# nixie_with_colon.net
KiCad netlist of a schematic drawn in EAGLE
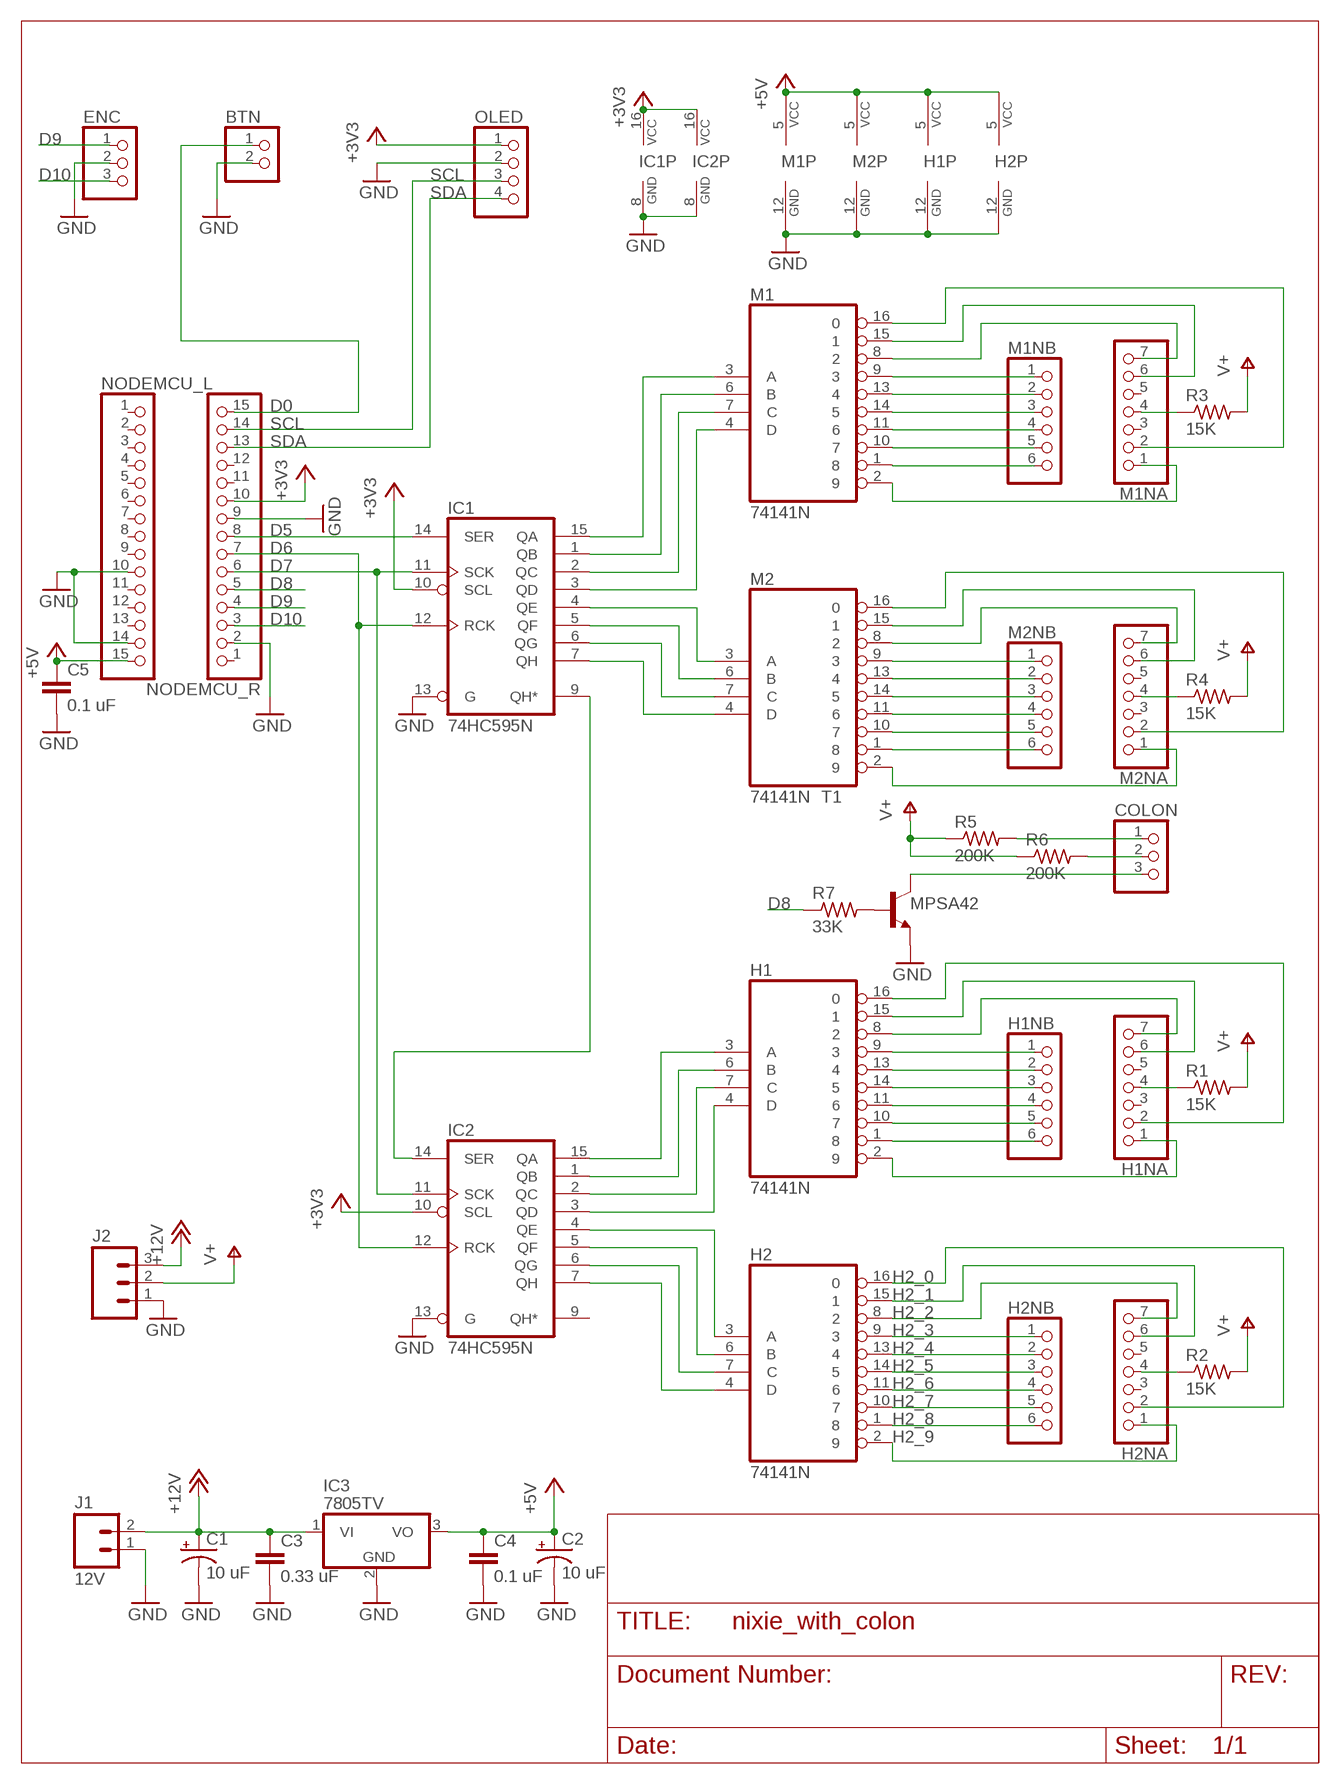
[diagram p0: schematic, sheet 1]

(export (version "E")
  (design (tool "Eeschema 10.0.6"))
  (components
    (comp (ref "BTN")
      (value "PINHD-1X2")
      (footprint "eagle-import:1X02")
      (libsource (lib "eagle-import") (part "PINHD-1X2"))
    )
    (comp (ref "C1")
      (value "10 uF")
      (footprint "eagle-import:E2,5-6")
      (libsource (lib "eagle-import") (part "CPOL-USE2.5-6"))
    )
    (comp (ref "C2")
      (value "10 uF")
      (footprint "eagle-import:E2,5-6")
      (libsource (lib "eagle-import") (part "CPOL-USE2.5-6"))
    )
    (comp (ref "C3")
      (value "0.33 uF")
      (footprint "eagle-import:C050-025X075")
      (libsource (lib "eagle-import") (part "C-EU050-025X075"))
    )
    (comp (ref "C4")
      (value "0.1 uF")
      (footprint "eagle-import:C050-025X075")
      (libsource (lib "eagle-import") (part "C-EU050-025X075"))
    )
    (comp (ref "C5")
      (value "0.1 uF")
      (footprint "eagle-import:C050-025X075")
      (libsource (lib "eagle-import") (part "C-EU050-025X075"))
    )
    (comp (ref "COLON")
      (value "PINHD-1X3")
      (footprint "eagle-import:1X03")
      (libsource (lib "eagle-import") (part "PINHD-1X3"))
    )
    (comp (ref "ENC")
      (value "PINHD-1X3")
      (footprint "eagle-import:1X03")
      (libsource (lib "eagle-import") (part "PINHD-1X3"))
    )
    (comp (ref "H1")
      (value "74141N")
      (footprint "eagle-import:DIL16")
      (libsource (lib "eagle-import") (part "74141N"))
    )
    (comp (ref "H1NA")
      (value "PINHD-1X7")
      (footprint "eagle-import:1X07")
      (libsource (lib "eagle-import") (part "PINHD-1X7"))
    )
    (comp (ref "H1NB")
      (value "PINHD-1X6")
      (footprint "eagle-import:1X06")
      (libsource (lib "eagle-import") (part "PINHD-1X6"))
    )
    (comp (ref "H2")
      (value "74141N")
      (footprint "eagle-import:DIL16")
      (libsource (lib "eagle-import") (part "74141N"))
    )
    (comp (ref "H2NA")
      (value "PINHD-1X7")
      (footprint "eagle-import:1X07")
      (libsource (lib "eagle-import") (part "PINHD-1X7"))
    )
    (comp (ref "H2NB")
      (value "PINHD-1X6")
      (footprint "eagle-import:1X06")
      (libsource (lib "eagle-import") (part "PINHD-1X6"))
    )
    (comp (ref "IC1")
      (value "74HC595N")
      (footprint "eagle-import:DIL16")
      (libsource (lib "eagle-import") (part "74595NHC"))
    )
    (comp (ref "IC2")
      (value "74HC595N")
      (footprint "eagle-import:DIL16")
      (libsource (lib "eagle-import") (part "74595NHC"))
    )
    (comp (ref "IC3")
      (value "7805TV")
      (footprint "eagle-import:TO220V")
      (libsource (lib "eagle-import") (part "78TV05"))
    )
    (comp (ref "J1")
      (value "12V")
      (footprint "eagle-import:SCREWTERMINAL-5MM-2")
      (libsource (lib "eagle-import") (part "M025MM"))
    )
    (comp (ref "J2")
      (value "M03-SCREW-5MM")
      (footprint "eagle-import:SCREWTERMINAL-5MM-3")
      (libsource (lib "eagle-import") (part "M03-SCREW-5MM"))
    )
    (comp (ref "M1")
      (value "74141N")
      (footprint "eagle-import:DIL16")
      (libsource (lib "eagle-import") (part "74141N"))
    )
    (comp (ref "M1NA")
      (value "PINHD-1X7")
      (footprint "eagle-import:1X07")
      (libsource (lib "eagle-import") (part "PINHD-1X7"))
    )
    (comp (ref "M1NB")
      (value "PINHD-1X6")
      (footprint "eagle-import:1X06")
      (libsource (lib "eagle-import") (part "PINHD-1X6"))
    )
    (comp (ref "M2")
      (value "74141N")
      (footprint "eagle-import:DIL16")
      (libsource (lib "eagle-import") (part "74141N"))
    )
    (comp (ref "M2NA")
      (value "PINHD-1X7")
      (footprint "eagle-import:1X07")
      (libsource (lib "eagle-import") (part "PINHD-1X7"))
    )
    (comp (ref "M2NB")
      (value "PINHD-1X6")
      (footprint "eagle-import:1X06")
      (libsource (lib "eagle-import") (part "PINHD-1X6"))
    )
    (comp (ref "NODEMCU_L")
      (value "PINHD-1X15")
      (footprint "eagle-import:1X15")
      (libsource (lib "eagle-import") (part "PINHD-1X15"))
    )
    (comp (ref "NODEMCU_R")
      (value "PINHD-1X15")
      (footprint "eagle-import:1X15")
      (libsource (lib "eagle-import") (part "PINHD-1X15"))
    )
    (comp (ref "OLED")
      (value "PINHD-1X4")
      (footprint "eagle-import:1X04")
      (libsource (lib "eagle-import") (part "PINHD-1X4"))
    )
    (comp (ref "R1")
      (value "15K")
      (footprint "eagle-import:0207_10")
      (libsource (lib "eagle-import") (part "R-US_0207/10"))
    )
    (comp (ref "R2")
      (value "15K")
      (footprint "eagle-import:0207_10")
      (libsource (lib "eagle-import") (part "R-US_0207/10"))
    )
    (comp (ref "R3")
      (value "15K")
      (footprint "eagle-import:0207_10")
      (libsource (lib "eagle-import") (part "R-US_0207/10"))
    )
    (comp (ref "R4")
      (value "15K")
      (footprint "eagle-import:0207_10")
      (libsource (lib "eagle-import") (part "R-US_0207/10"))
    )
    (comp (ref "R5")
      (value "200K")
      (footprint "eagle-import:0207_10")
      (libsource (lib "eagle-import") (part "R-US_0207/10"))
    )
    (comp (ref "R6")
      (value "200K")
      (footprint "eagle-import:0207_10")
      (libsource (lib "eagle-import") (part "R-US_0207/10"))
    )
    (comp (ref "R7")
      (value "33K")
      (footprint "eagle-import:0207_10")
      (libsource (lib "eagle-import") (part "R-US_0207/10"))
    )
    (comp (ref "T1")
      (value "MPSA42")
      (footprint "eagle-import:TO92-EBC")
      (libsource (lib "eagle-import") (part "-NPN-TO92-EBCMPSA42"))
    )
  )
  (nets
    (net (code "1") (name "+3V3") (class "Default")
      (node (ref "IC1") (pin "10") (pinfunction "SCL_10") (pintype "input"))
      (node (ref "IC1") (pin "16") (pinfunction "VCC_16") (pintype "power_in"))
      (node (ref "IC2") (pin "10") (pinfunction "SCL_10") (pintype "input"))
      (node (ref "IC2") (pin "16") (pinfunction "VCC_16") (pintype "power_in"))
      (node (ref "NODEMCU_R") (pin "10") (pinfunction "10_10") (pintype "passive"))
      (node (ref "OLED") (pin "1") (pinfunction "1_1") (pintype "passive"))
    )
    (net (code "2") (name "+5V") (class "Default")
      (node (ref "C2") (pin "+") (pinfunction "+_+") (pintype "passive"))
      (node (ref "C4") (pin "1") (pinfunction "1_1") (pintype "passive"))
      (node (ref "C5") (pin "1") (pinfunction "1_1") (pintype "passive"))
      (node (ref "H1") (pin "5") (pinfunction "VCC_5") (pintype "power_in"))
      (node (ref "H2") (pin "5") (pinfunction "VCC_5") (pintype "power_in"))
      (node (ref "IC3") (pin "3") (pinfunction "VO_3") (pintype "passive"))
      (node (ref "M1") (pin "5") (pinfunction "VCC_5") (pintype "power_in"))
      (node (ref "M2") (pin "5") (pinfunction "VCC_5") (pintype "power_in"))
      (node (ref "NODEMCU_L") (pin "15") (pinfunction "15_15") (pintype "passive"))
    )
    (net (code "3") (name "+12V") (class "Default")
      (node (ref "C1") (pin "+") (pinfunction "+_+") (pintype "passive"))
      (node (ref "C3") (pin "1") (pinfunction "1_1") (pintype "passive"))
      (node (ref "IC3") (pin "1") (pinfunction "VI_1") (pintype "input"))
      (node (ref "J1") (pin "2") (pinfunction "2_2") (pintype "passive"))
      (node (ref "J2") (pin "3") (pinfunction "3_3") (pintype "passive"))
    )
    (net (code "4") (name "/D0") (class "Default")
      (node (ref "BTN") (pin "1") (pinfunction "1_1") (pintype "passive"))
      (node (ref "NODEMCU_R") (pin "15") (pinfunction "15_15") (pintype "passive"))
    )
    (net (code "5") (name "/D5") (class "Default")
      (node (ref "IC1") (pin "14") (pinfunction "SER_14") (pintype "input"))
      (node (ref "NODEMCU_R") (pin "8") (pinfunction "8_8") (pintype "passive"))
    )
    (net (code "6") (name "/D6") (class "Default")
      (node (ref "IC1") (pin "12") (pinfunction "RCK_12") (pintype "input"))
      (node (ref "IC2") (pin "12") (pinfunction "RCK_12") (pintype "input"))
      (node (ref "NODEMCU_R") (pin "7") (pinfunction "7_7") (pintype "passive"))
    )
    (net (code "7") (name "/D7") (class "Default")
      (node (ref "IC1") (pin "11") (pinfunction "SCK_11") (pintype "input"))
      (node (ref "IC2") (pin "11") (pinfunction "SCK_11") (pintype "input"))
      (node (ref "NODEMCU_R") (pin "6") (pinfunction "6_6") (pintype "passive"))
    )
    (net (code "8") (name "/D8") (class "Default")
      (node (ref "NODEMCU_R") (pin "5") (pinfunction "5_5") (pintype "passive"))
      (node (ref "R7") (pin "1") (pinfunction "1_1") (pintype "passive"))
    )
    (net (code "9") (name "/D9") (class "Default")
      (node (ref "ENC") (pin "1") (pinfunction "1_1") (pintype "passive"))
      (node (ref "NODEMCU_R") (pin "4") (pinfunction "4_4") (pintype "passive"))
    )
    (net (code "10") (name "/D10") (class "Default")
      (node (ref "ENC") (pin "3") (pinfunction "3_3") (pintype "passive"))
      (node (ref "NODEMCU_R") (pin "3") (pinfunction "3_3") (pintype "passive"))
    )
    (net (code "11") (name "/H2_0") (class "Default")
      (node (ref "H2") (pin "16") (pinfunction "0_16") (pintype "open_collector"))
      (node (ref "H2NA") (pin "2") (pinfunction "2_2") (pintype "passive"))
    )
    (net (code "12") (name "/H2_1") (class "Default")
      (node (ref "H2") (pin "15") (pinfunction "1_15") (pintype "open_collector"))
      (node (ref "H2NA") (pin "6") (pinfunction "6_6") (pintype "passive"))
    )
    (net (code "13") (name "/H2_2") (class "Default")
      (node (ref "H2") (pin "8") (pinfunction "2_8") (pintype "open_collector"))
      (node (ref "H2NA") (pin "7") (pinfunction "7_7") (pintype "passive"))
    )
    (net (code "14") (name "/H2_3") (class "Default")
      (node (ref "H2") (pin "9") (pinfunction "3_9") (pintype "open_collector"))
      (node (ref "H2NB") (pin "1") (pinfunction "1_1") (pintype "passive"))
    )
    (net (code "15") (name "/H2_4") (class "Default")
      (node (ref "H2") (pin "13") (pinfunction "4_13") (pintype "open_collector"))
      (node (ref "H2NB") (pin "2") (pinfunction "2_2") (pintype "passive"))
    )
    (net (code "16") (name "/H2_5") (class "Default")
      (node (ref "H2") (pin "14") (pinfunction "5_14") (pintype "open_collector"))
      (node (ref "H2NB") (pin "3") (pinfunction "3_3") (pintype "passive"))
    )
    (net (code "17") (name "/H2_6") (class "Default")
      (node (ref "H2") (pin "11") (pinfunction "6_11") (pintype "open_collector"))
      (node (ref "H2NB") (pin "4") (pinfunction "4_4") (pintype "passive"))
    )
    (net (code "18") (name "/H2_7") (class "Default")
      (node (ref "H2") (pin "10") (pinfunction "7_10") (pintype "open_collector"))
      (node (ref "H2NB") (pin "5") (pinfunction "5_5") (pintype "passive"))
    )
    (net (code "19") (name "/H2_8") (class "Default")
      (node (ref "H2") (pin "1") (pinfunction "8_1") (pintype "open_collector"))
      (node (ref "H2NB") (pin "6") (pinfunction "6_6") (pintype "passive"))
    )
    (net (code "20") (name "/H2_9") (class "Default")
      (node (ref "H2") (pin "2") (pinfunction "9_2") (pintype "open_collector"))
      (node (ref "H2NA") (pin "1") (pinfunction "1_1") (pintype "passive"))
    )
    (net (code "21") (name "/SCL") (class "Default")
      (node (ref "NODEMCU_R") (pin "14") (pinfunction "14_14") (pintype "passive"))
      (node (ref "OLED") (pin "3") (pinfunction "3_3") (pintype "passive"))
    )
    (net (code "22") (name "/SDA") (class "Default")
      (node (ref "NODEMCU_R") (pin "13") (pinfunction "13_13") (pintype "passive"))
      (node (ref "OLED") (pin "4") (pinfunction "4_4") (pintype "passive"))
    )
    (net (code "23") (name "GND") (class "Default")
      (node (ref "BTN") (pin "2") (pinfunction "2_2") (pintype "passive"))
      (node (ref "C1") (pin "-") (pinfunction "-_-") (pintype "passive"))
      (node (ref "C2") (pin "-") (pinfunction "-_-") (pintype "passive"))
      (node (ref "C3") (pin "2") (pinfunction "2_2") (pintype "passive"))
      (node (ref "C4") (pin "2") (pinfunction "2_2") (pintype "passive"))
      (node (ref "C5") (pin "2") (pinfunction "2_2") (pintype "passive"))
      (node (ref "ENC") (pin "2") (pinfunction "2_2") (pintype "passive"))
      (node (ref "H1") (pin "12") (pinfunction "GND_12") (pintype "power_in"))
      (node (ref "H2") (pin "12") (pinfunction "GND_12") (pintype "power_in"))
      (node (ref "IC1") (pin "13") (pinfunction "G_13") (pintype "input"))
      (node (ref "IC1") (pin "8") (pinfunction "GND_8") (pintype "power_in"))
      (node (ref "IC2") (pin "13") (pinfunction "G_13") (pintype "input"))
      (node (ref "IC2") (pin "8") (pinfunction "GND_8") (pintype "power_in"))
      (node (ref "IC3") (pin "2") (pinfunction "GND_2") (pintype "passive"))
      (node (ref "J1") (pin "1") (pinfunction "1_1") (pintype "passive"))
      (node (ref "J2") (pin "1") (pinfunction "1_1") (pintype "passive"))
      (node (ref "M1") (pin "12") (pinfunction "GND_12") (pintype "power_in"))
      (node (ref "M2") (pin "12") (pinfunction "GND_12") (pintype "power_in"))
      (node (ref "NODEMCU_L") (pin "10") (pinfunction "10_10") (pintype "passive"))
      (node (ref "NODEMCU_L") (pin "14") (pinfunction "14_14") (pintype "passive"))
      (node (ref "NODEMCU_R") (pin "2") (pinfunction "2_2") (pintype "passive"))
      (node (ref "NODEMCU_R") (pin "9") (pinfunction "9_9") (pintype "passive"))
      (node (ref "OLED") (pin "2") (pinfunction "2_2") (pintype "passive"))
      (node (ref "T1") (pin "E") (pinfunction "E_E") (pintype "passive"))
    )
    (net (code "24") (name "Net-(COLON-Pad1)") (class "Default")
      (node (ref "COLON") (pin "1") (pinfunction "1_1") (pintype "passive"))
      (node (ref "R5") (pin "2") (pinfunction "2_2") (pintype "passive"))
    )
    (net (code "25") (name "Net-(COLON-Pad2)") (class "Default")
      (node (ref "COLON") (pin "2") (pinfunction "2_2") (pintype "passive"))
      (node (ref "R6") (pin "2") (pinfunction "2_2") (pintype "passive"))
    )
    (net (code "26") (name "Net-(COLON-Pad3)") (class "Default")
      (node (ref "COLON") (pin "3") (pinfunction "3_3") (pintype "passive"))
      (node (ref "T1") (pin "C") (pinfunction "C_C") (pintype "passive"))
    )
    (net (code "27") (name "Net-(H1A-0)") (class "Default")
      (node (ref "H1") (pin "16") (pinfunction "0_16") (pintype "open_collector"))
      (node (ref "H1NA") (pin "2") (pinfunction "2_2") (pintype "passive"))
    )
    (net (code "28") (name "Net-(H1A-1)") (class "Default")
      (node (ref "H1") (pin "15") (pinfunction "1_15") (pintype "open_collector"))
      (node (ref "H1NA") (pin "6") (pinfunction "6_6") (pintype "passive"))
    )
    (net (code "29") (name "Net-(H1A-2)") (class "Default")
      (node (ref "H1") (pin "8") (pinfunction "2_8") (pintype "open_collector"))
      (node (ref "H1NA") (pin "7") (pinfunction "7_7") (pintype "passive"))
    )
    (net (code "30") (name "Net-(H1A-3)") (class "Default")
      (node (ref "H1") (pin "9") (pinfunction "3_9") (pintype "open_collector"))
      (node (ref "H1NB") (pin "1") (pinfunction "1_1") (pintype "passive"))
    )
    (net (code "31") (name "Net-(H1A-4)") (class "Default")
      (node (ref "H1") (pin "13") (pinfunction "4_13") (pintype "open_collector"))
      (node (ref "H1NB") (pin "2") (pinfunction "2_2") (pintype "passive"))
    )
    (net (code "32") (name "Net-(H1A-5)") (class "Default")
      (node (ref "H1") (pin "14") (pinfunction "5_14") (pintype "open_collector"))
      (node (ref "H1NB") (pin "3") (pinfunction "3_3") (pintype "passive"))
    )
    (net (code "33") (name "Net-(H1A-6)") (class "Default")
      (node (ref "H1") (pin "11") (pinfunction "6_11") (pintype "open_collector"))
      (node (ref "H1NB") (pin "4") (pinfunction "4_4") (pintype "passive"))
    )
    (net (code "34") (name "Net-(H1A-7)") (class "Default")
      (node (ref "H1") (pin "10") (pinfunction "7_10") (pintype "open_collector"))
      (node (ref "H1NB") (pin "5") (pinfunction "5_5") (pintype "passive"))
    )
    (net (code "35") (name "Net-(H1A-8)") (class "Default")
      (node (ref "H1") (pin "1") (pinfunction "8_1") (pintype "open_collector"))
      (node (ref "H1NB") (pin "6") (pinfunction "6_6") (pintype "passive"))
    )
    (net (code "36") (name "Net-(H1A-9)") (class "Default")
      (node (ref "H1") (pin "2") (pinfunction "9_2") (pintype "open_collector"))
      (node (ref "H1NA") (pin "1") (pinfunction "1_1") (pintype "passive"))
    )
    (net (code "37") (name "Net-(H1A-A)") (class "Default")
      (node (ref "H1") (pin "3") (pinfunction "A_3") (pintype "input"))
      (node (ref "IC2") (pin "15") (pinfunction "QA_15") (pintype "tri_state"))
    )
    (net (code "38") (name "Net-(H1A-B)") (class "Default")
      (node (ref "H1") (pin "6") (pinfunction "B_6") (pintype "input"))
      (node (ref "IC2") (pin "1") (pinfunction "QB_1") (pintype "tri_state"))
    )
    (net (code "39") (name "Net-(H1A-C)") (class "Default")
      (node (ref "H1") (pin "7") (pinfunction "C_7") (pintype "input"))
      (node (ref "IC2") (pin "2") (pinfunction "QC_2") (pintype "tri_state"))
    )
    (net (code "40") (name "Net-(H1A-D)") (class "Default")
      (node (ref "H1") (pin "4") (pinfunction "D_4") (pintype "input"))
      (node (ref "IC2") (pin "3") (pinfunction "QD_3") (pintype "tri_state"))
    )
    (net (code "41") (name "Net-(H1NA-Pad4)") (class "Default")
      (node (ref "H1NA") (pin "4") (pinfunction "4_4") (pintype "passive"))
      (node (ref "R1") (pin "1") (pinfunction "1_1") (pintype "passive"))
    )
    (net (code "42") (name "Net-(H2A-A)") (class "Default")
      (node (ref "H2") (pin "3") (pinfunction "A_3") (pintype "input"))
      (node (ref "IC2") (pin "4") (pinfunction "QE_4") (pintype "tri_state"))
    )
    (net (code "43") (name "Net-(H2A-B)") (class "Default")
      (node (ref "H2") (pin "6") (pinfunction "B_6") (pintype "input"))
      (node (ref "IC2") (pin "5") (pinfunction "QF_5") (pintype "tri_state"))
    )
    (net (code "44") (name "Net-(H2A-C)") (class "Default")
      (node (ref "H2") (pin "7") (pinfunction "C_7") (pintype "input"))
      (node (ref "IC2") (pin "6") (pinfunction "QG_6") (pintype "tri_state"))
    )
    (net (code "45") (name "Net-(H2A-D)") (class "Default")
      (node (ref "H2") (pin "4") (pinfunction "D_4") (pintype "input"))
      (node (ref "IC2") (pin "7") (pinfunction "QH_7") (pintype "tri_state"))
    )
    (net (code "46") (name "Net-(H2NA-Pad4)") (class "Default")
      (node (ref "H2NA") (pin "4") (pinfunction "4_4") (pintype "passive"))
      (node (ref "R2") (pin "1") (pinfunction "1_1") (pintype "passive"))
    )
    (net (code "47") (name "Net-(IC1A-QA)") (class "Default")
      (node (ref "IC1") (pin "15") (pinfunction "QA_15") (pintype "tri_state"))
      (node (ref "M1") (pin "3") (pinfunction "A_3") (pintype "input"))
    )
    (net (code "48") (name "Net-(IC1A-QB)") (class "Default")
      (node (ref "IC1") (pin "1") (pinfunction "QB_1") (pintype "tri_state"))
      (node (ref "M1") (pin "6") (pinfunction "B_6") (pintype "input"))
    )
    (net (code "49") (name "Net-(IC1A-QC)") (class "Default")
      (node (ref "IC1") (pin "2") (pinfunction "QC_2") (pintype "tri_state"))
      (node (ref "M1") (pin "7") (pinfunction "C_7") (pintype "input"))
    )
    (net (code "50") (name "Net-(IC1A-QD)") (class "Default")
      (node (ref "IC1") (pin "3") (pinfunction "QD_3") (pintype "tri_state"))
      (node (ref "M1") (pin "4") (pinfunction "D_4") (pintype "input"))
    )
    (net (code "51") (name "Net-(IC1A-QE)") (class "Default")
      (node (ref "IC1") (pin "4") (pinfunction "QE_4") (pintype "tri_state"))
      (node (ref "M2") (pin "3") (pinfunction "A_3") (pintype "input"))
    )
    (net (code "52") (name "Net-(IC1A-QF)") (class "Default")
      (node (ref "IC1") (pin "5") (pinfunction "QF_5") (pintype "tri_state"))
      (node (ref "M2") (pin "6") (pinfunction "B_6") (pintype "input"))
    )
    (net (code "53") (name "Net-(IC1A-QG)") (class "Default")
      (node (ref "IC1") (pin "6") (pinfunction "QG_6") (pintype "tri_state"))
      (node (ref "M2") (pin "7") (pinfunction "C_7") (pintype "input"))
    )
    (net (code "54") (name "Net-(IC1A-QH)") (class "Default")
      (node (ref "IC1") (pin "7") (pinfunction "QH_7") (pintype "tri_state"))
      (node (ref "M2") (pin "4") (pinfunction "D_4") (pintype "input"))
    )
    (net (code "55") (name "Net-(IC1A-QH*)") (class "Default")
      (node (ref "IC1") (pin "9") (pinfunction "QH*_9") (pintype "tri_state"))
      (node (ref "IC2") (pin "14") (pinfunction "SER_14") (pintype "input"))
    )
    (net (code "56") (name "Net-(M1A-0)") (class "Default")
      (node (ref "M1") (pin "16") (pinfunction "0_16") (pintype "open_collector"))
      (node (ref "M1NA") (pin "2") (pinfunction "2_2") (pintype "passive"))
    )
    (net (code "57") (name "Net-(M1A-1)") (class "Default")
      (node (ref "M1") (pin "15") (pinfunction "1_15") (pintype "open_collector"))
      (node (ref "M1NA") (pin "6") (pinfunction "6_6") (pintype "passive"))
    )
    (net (code "58") (name "Net-(M1A-2)") (class "Default")
      (node (ref "M1") (pin "8") (pinfunction "2_8") (pintype "open_collector"))
      (node (ref "M1NA") (pin "7") (pinfunction "7_7") (pintype "passive"))
    )
    (net (code "59") (name "Net-(M1A-3)") (class "Default")
      (node (ref "M1") (pin "9") (pinfunction "3_9") (pintype "open_collector"))
      (node (ref "M1NB") (pin "1") (pinfunction "1_1") (pintype "passive"))
    )
    (net (code "60") (name "Net-(M1A-4)") (class "Default")
      (node (ref "M1") (pin "13") (pinfunction "4_13") (pintype "open_collector"))
      (node (ref "M1NB") (pin "2") (pinfunction "2_2") (pintype "passive"))
    )
    (net (code "61") (name "Net-(M1A-5)") (class "Default")
      (node (ref "M1") (pin "14") (pinfunction "5_14") (pintype "open_collector"))
      (node (ref "M1NB") (pin "3") (pinfunction "3_3") (pintype "passive"))
    )
    (net (code "62") (name "Net-(M1A-6)") (class "Default")
      (node (ref "M1") (pin "11") (pinfunction "6_11") (pintype "open_collector"))
      (node (ref "M1NB") (pin "4") (pinfunction "4_4") (pintype "passive"))
    )
    (net (code "63") (name "Net-(M1A-7)") (class "Default")
      (node (ref "M1") (pin "10") (pinfunction "7_10") (pintype "open_collector"))
      (node (ref "M1NB") (pin "5") (pinfunction "5_5") (pintype "passive"))
    )
    (net (code "64") (name "Net-(M1A-8)") (class "Default")
      (node (ref "M1") (pin "1") (pinfunction "8_1") (pintype "open_collector"))
      (node (ref "M1NB") (pin "6") (pinfunction "6_6") (pintype "passive"))
    )
    (net (code "65") (name "Net-(M1A-9)") (class "Default")
      (node (ref "M1") (pin "2") (pinfunction "9_2") (pintype "open_collector"))
      (node (ref "M1NA") (pin "1") (pinfunction "1_1") (pintype "passive"))
    )
    (net (code "66") (name "Net-(M1NA-Pad4)") (class "Default")
      (node (ref "M1NA") (pin "4") (pinfunction "4_4") (pintype "passive"))
      (node (ref "R3") (pin "1") (pinfunction "1_1") (pintype "passive"))
    )
    (net (code "67") (name "Net-(M2A-0)") (class "Default")
      (node (ref "M2") (pin "16") (pinfunction "0_16") (pintype "open_collector"))
      (node (ref "M2NA") (pin "2") (pinfunction "2_2") (pintype "passive"))
    )
    (net (code "68") (name "Net-(M2A-1)") (class "Default")
      (node (ref "M2") (pin "15") (pinfunction "1_15") (pintype "open_collector"))
      (node (ref "M2NA") (pin "6") (pinfunction "6_6") (pintype "passive"))
    )
    (net (code "69") (name "Net-(M2A-2)") (class "Default")
      (node (ref "M2") (pin "8") (pinfunction "2_8") (pintype "open_collector"))
      (node (ref "M2NA") (pin "7") (pinfunction "7_7") (pintype "passive"))
    )
    (net (code "70") (name "Net-(M2A-3)") (class "Default")
      (node (ref "M2") (pin "9") (pinfunction "3_9") (pintype "open_collector"))
      (node (ref "M2NB") (pin "1") (pinfunction "1_1") (pintype "passive"))
    )
    (net (code "71") (name "Net-(M2A-4)") (class "Default")
      (node (ref "M2") (pin "13") (pinfunction "4_13") (pintype "open_collector"))
      (node (ref "M2NB") (pin "2") (pinfunction "2_2") (pintype "passive"))
    )
    (net (code "72") (name "Net-(M2A-5)") (class "Default")
      (node (ref "M2") (pin "14") (pinfunction "5_14") (pintype "open_collector"))
      (node (ref "M2NB") (pin "3") (pinfunction "3_3") (pintype "passive"))
    )
    (net (code "73") (name "Net-(M2A-6)") (class "Default")
      (node (ref "M2") (pin "11") (pinfunction "6_11") (pintype "open_collector"))
      (node (ref "M2NB") (pin "4") (pinfunction "4_4") (pintype "passive"))
    )
    (net (code "74") (name "Net-(M2A-7)") (class "Default")
      (node (ref "M2") (pin "10") (pinfunction "7_10") (pintype "open_collector"))
      (node (ref "M2NB") (pin "5") (pinfunction "5_5") (pintype "passive"))
    )
    (net (code "75") (name "Net-(M2A-8)") (class "Default")
      (node (ref "M2") (pin "1") (pinfunction "8_1") (pintype "open_collector"))
      (node (ref "M2NB") (pin "6") (pinfunction "6_6") (pintype "passive"))
    )
    (net (code "76") (name "Net-(M2A-9)") (class "Default")
      (node (ref "M2") (pin "2") (pinfunction "9_2") (pintype "open_collector"))
      (node (ref "M2NA") (pin "1") (pinfunction "1_1") (pintype "passive"))
    )
    (net (code "77") (name "Net-(M2NA-Pad4)") (class "Default")
      (node (ref "M2NA") (pin "4") (pinfunction "4_4") (pintype "passive"))
      (node (ref "R4") (pin "1") (pinfunction "1_1") (pintype "passive"))
    )
    (net (code "78") (name "Net-(R7-Pad2)") (class "Default")
      (node (ref "R7") (pin "2") (pinfunction "2_2") (pintype "passive"))
      (node (ref "T1") (pin "B") (pinfunction "B_B") (pintype "passive"))
    )
    (net (code "79") (name "V+") (class "Default")
      (node (ref "J2") (pin "2") (pinfunction "2_2") (pintype "passive"))
      (node (ref "R1") (pin "2") (pinfunction "2_2") (pintype "passive"))
      (node (ref "R2") (pin "2") (pinfunction "2_2") (pintype "passive"))
      (node (ref "R3") (pin "2") (pinfunction "2_2") (pintype "passive"))
      (node (ref "R4") (pin "2") (pinfunction "2_2") (pintype "passive"))
      (node (ref "R5") (pin "1") (pinfunction "1_1") (pintype "passive"))
      (node (ref "R6") (pin "1") (pinfunction "1_1") (pintype "passive"))
    )
    (net (code "80") (name "unconnected-(H1NA-Pad3)") (class "Default")
      (node (ref "H1NA") (pin "3") (pinfunction "3_3") (pintype "passive"))
    )
    (net (code "81") (name "unconnected-(H1NA-Pad5)") (class "Default")
      (node (ref "H1NA") (pin "5") (pinfunction "5_5") (pintype "passive"))
    )
    (net (code "82") (name "unconnected-(H2NA-Pad3)") (class "Default")
      (node (ref "H2NA") (pin "3") (pinfunction "3_3") (pintype "passive"))
    )
    (net (code "83") (name "unconnected-(H2NA-Pad5)") (class "Default")
      (node (ref "H2NA") (pin "5") (pinfunction "5_5") (pintype "passive"))
    )
    (net (code "84") (name "unconnected-(IC2A-QH*-Pad9)") (class "Default")
      (node (ref "IC2") (pin "9") (pinfunction "QH*_9") (pintype "tri_state"))
    )
    (net (code "85") (name "unconnected-(M1NA-Pad3)") (class "Default")
      (node (ref "M1NA") (pin "3") (pinfunction "3_3") (pintype "passive"))
    )
    (net (code "86") (name "unconnected-(M1NA-Pad5)") (class "Default")
      (node (ref "M1NA") (pin "5") (pinfunction "5_5") (pintype "passive"))
    )
    (net (code "87") (name "unconnected-(M2NA-Pad3)") (class "Default")
      (node (ref "M2NA") (pin "3") (pinfunction "3_3") (pintype "passive"))
    )
    (net (code "88") (name "unconnected-(M2NA-Pad5)") (class "Default")
      (node (ref "M2NA") (pin "5") (pinfunction "5_5") (pintype "passive"))
    )
    (net (code "89") (name "unconnected-(NODEMCU_L-Pad1)") (class "Default")
      (node (ref "NODEMCU_L") (pin "1") (pinfunction "1_1") (pintype "passive"))
    )
    (net (code "90") (name "unconnected-(NODEMCU_L-Pad2)") (class "Default")
      (node (ref "NODEMCU_L") (pin "2") (pinfunction "2_2") (pintype "passive"))
    )
    (net (code "91") (name "unconnected-(NODEMCU_L-Pad3)") (class "Default")
      (node (ref "NODEMCU_L") (pin "3") (pinfunction "3_3") (pintype "passive"))
    )
    (net (code "92") (name "unconnected-(NODEMCU_L-Pad4)") (class "Default")
      (node (ref "NODEMCU_L") (pin "4") (pinfunction "4_4") (pintype "passive"))
    )
    (net (code "93") (name "unconnected-(NODEMCU_L-Pad5)") (class "Default")
      (node (ref "NODEMCU_L") (pin "5") (pinfunction "5_5") (pintype "passive"))
    )
    (net (code "94") (name "unconnected-(NODEMCU_L-Pad6)") (class "Default")
      (node (ref "NODEMCU_L") (pin "6") (pinfunction "6_6") (pintype "passive"))
    )
    (net (code "95") (name "unconnected-(NODEMCU_L-Pad7)") (class "Default")
      (node (ref "NODEMCU_L") (pin "7") (pinfunction "7_7") (pintype "passive"))
    )
    (net (code "96") (name "unconnected-(NODEMCU_L-Pad8)") (class "Default")
      (node (ref "NODEMCU_L") (pin "8") (pinfunction "8_8") (pintype "passive"))
    )
    (net (code "97") (name "unconnected-(NODEMCU_L-Pad9)") (class "Default")
      (node (ref "NODEMCU_L") (pin "9") (pinfunction "9_9") (pintype "passive"))
    )
    (net (code "98") (name "unconnected-(NODEMCU_L-Pad11)") (class "Default")
      (node (ref "NODEMCU_L") (pin "11") (pinfunction "11_11") (pintype "passive"))
    )
    (net (code "99") (name "unconnected-(NODEMCU_L-Pad12)") (class "Default")
      (node (ref "NODEMCU_L") (pin "12") (pinfunction "12_12") (pintype "passive"))
    )
    (net (code "100") (name "unconnected-(NODEMCU_L-Pad13)") (class "Default")
      (node (ref "NODEMCU_L") (pin "13") (pinfunction "13_13") (pintype "passive"))
    )
    (net (code "101") (name "unconnected-(NODEMCU_R-Pad1)") (class "Default")
      (node (ref "NODEMCU_R") (pin "1") (pinfunction "1_1") (pintype "passive"))
    )
    (net (code "102") (name "unconnected-(NODEMCU_R-Pad11)") (class "Default")
      (node (ref "NODEMCU_R") (pin "11") (pinfunction "11_11") (pintype "passive"))
    )
    (net (code "103") (name "unconnected-(NODEMCU_R-Pad12)") (class "Default")
      (node (ref "NODEMCU_R") (pin "12") (pinfunction "12_12") (pintype "passive"))
    )
  )
)
